# PowerBoard.net
KiCad netlist of a schematic drawn in EAGLE
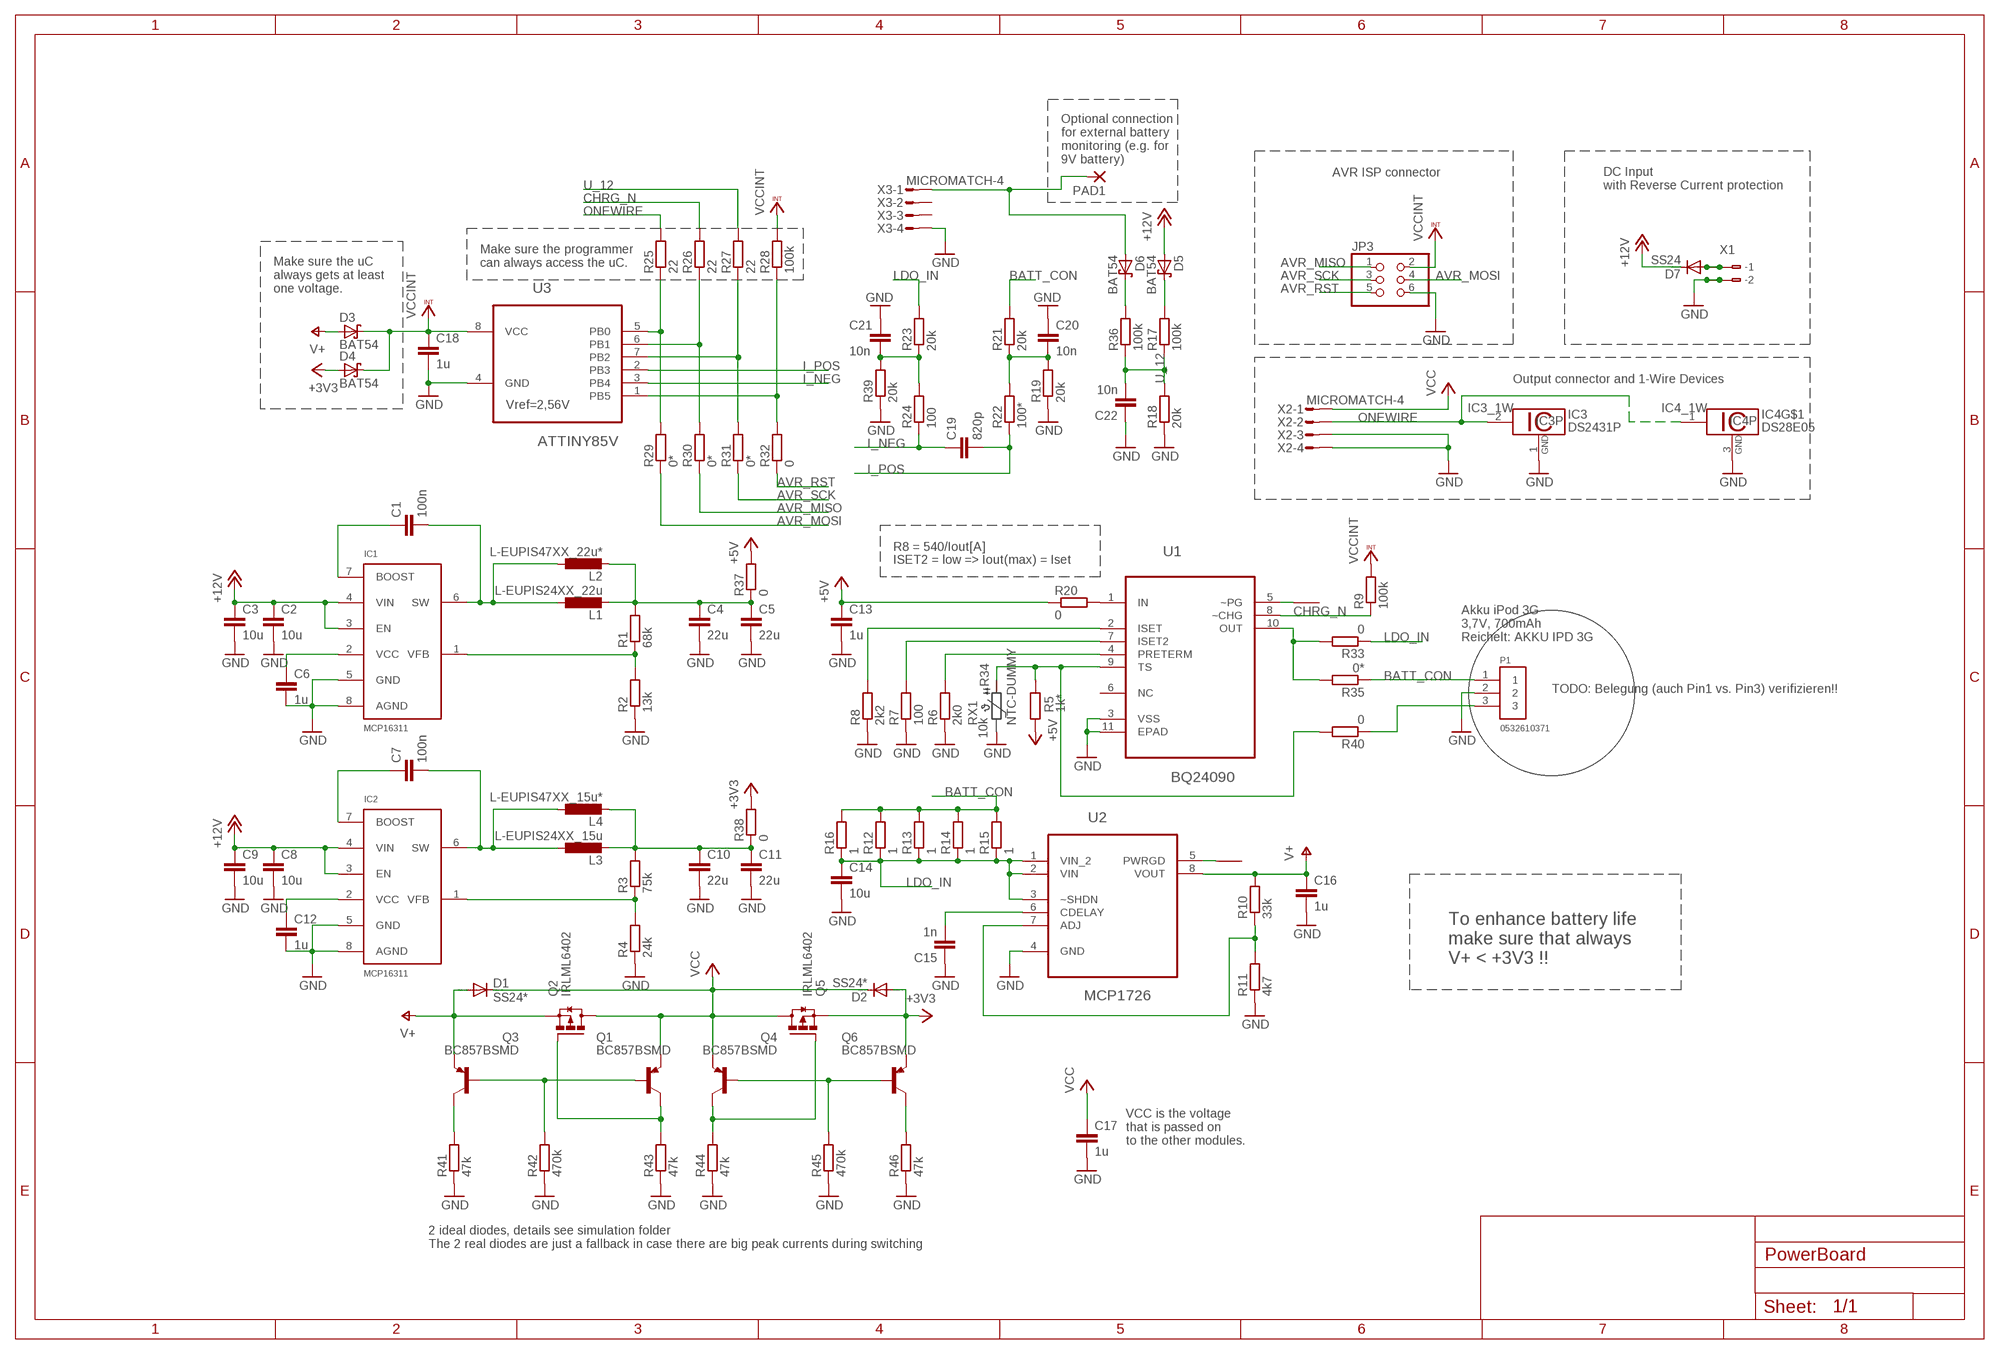
[diagram p0: schematic, sheet 1]

(export (version "E")
  (design (tool "Eeschema 10.0.6"))
  (components
    (comp (ref "C1")
      (value "100n")
      (footprint "eagle-import:C0603")
      (libsource (lib "eagle-import") (part "C-EUC0603"))
    )
    (comp (ref "C2")
      (value "10u")
      (footprint "eagle-import:C1210")
      (libsource (lib "eagle-import") (part "C-EUC1210"))
    )
    (comp (ref "C3")
      (value "10u")
      (footprint "eagle-import:C1210")
      (libsource (lib "eagle-import") (part "C-EUC1210"))
    )
    (comp (ref "C4")
      (value "22u")
      (footprint "eagle-import:C1210")
      (libsource (lib "eagle-import") (part "C-EUC1210"))
    )
    (comp (ref "C5")
      (value "22u")
      (footprint "eagle-import:C1210")
      (libsource (lib "eagle-import") (part "C-EUC1210"))
    )
    (comp (ref "C6")
      (value "1u")
      (footprint "eagle-import:C0603")
      (libsource (lib "eagle-import") (part "C-EUC0603"))
    )
    (comp (ref "C7")
      (value "100n")
      (footprint "eagle-import:C0603")
      (libsource (lib "eagle-import") (part "C-EUC0603"))
    )
    (comp (ref "C8")
      (value "10u")
      (footprint "eagle-import:C1210")
      (libsource (lib "eagle-import") (part "C-EUC1210"))
    )
    (comp (ref "C9")
      (value "10u")
      (footprint "eagle-import:C1210")
      (libsource (lib "eagle-import") (part "C-EUC1210"))
    )
    (comp (ref "C10")
      (value "22u")
      (footprint "eagle-import:C1210")
      (libsource (lib "eagle-import") (part "C-EUC1210"))
    )
    (comp (ref "C11")
      (value "22u")
      (footprint "eagle-import:C1210")
      (libsource (lib "eagle-import") (part "C-EUC1210"))
    )
    (comp (ref "C12")
      (value "1u")
      (footprint "eagle-import:C0603")
      (libsource (lib "eagle-import") (part "C-EUC0603"))
    )
    (comp (ref "C13")
      (value "1u")
      (footprint "eagle-import:C0603")
      (libsource (lib "eagle-import") (part "C-EUC0603"))
    )
    (comp (ref "C14")
      (value "10u")
      (footprint "eagle-import:C1210")
      (libsource (lib "eagle-import") (part "C-EUC1210"))
    )
    (comp (ref "C15")
      (value "1n")
      (footprint "eagle-import:C0603")
      (libsource (lib "eagle-import") (part "C-EUC0603"))
    )
    (comp (ref "C16")
      (value "1u")
      (footprint "eagle-import:C0603")
      (libsource (lib "eagle-import") (part "C-EUC0603"))
    )
    (comp (ref "C17")
      (value "1u")
      (footprint "eagle-import:C0603")
      (libsource (lib "eagle-import") (part "C-EUC0603"))
    )
    (comp (ref "C18")
      (value "1u")
      (footprint "eagle-import:C0603")
      (libsource (lib "eagle-import") (part "C-EUC0603"))
    )
    (comp (ref "C19")
      (value "820p")
      (footprint "eagle-import:C0603")
      (libsource (lib "eagle-import") (part "C-EUC0603"))
    )
    (comp (ref "C20")
      (value "10n")
      (footprint "eagle-import:C0603")
      (libsource (lib "eagle-import") (part "C-EUC0603"))
    )
    (comp (ref "C21")
      (value "10n")
      (footprint "eagle-import:C0603")
      (libsource (lib "eagle-import") (part "C-EUC0603"))
    )
    (comp (ref "C22")
      (value "10n")
      (footprint "eagle-import:C0603")
      (libsource (lib "eagle-import") (part "C-EUC0603"))
    )
    (comp (ref "D1")
      (value "SS24*")
      (footprint "eagle-import:SMB")
      (libsource (lib "eagle-import") (part "DIODE-SMB"))
    )
    (comp (ref "D2")
      (value "SS24*")
      (footprint "eagle-import:SMB")
      (libsource (lib "eagle-import") (part "DIODE-SMB"))
    )
    (comp (ref "D3")
      (value "BAT54")
      (footprint "eagle-import:SOT23")
      (libsource (lib "eagle-import") (part "BAT54"))
    )
    (comp (ref "D4")
      (value "BAT54")
      (footprint "eagle-import:SOT23")
      (libsource (lib "eagle-import") (part "BAT54"))
    )
    (comp (ref "D5")
      (value "BAT54")
      (footprint "eagle-import:SOT23")
      (libsource (lib "eagle-import") (part "BAT54"))
    )
    (comp (ref "D6")
      (value "BAT54")
      (footprint "eagle-import:SOT23")
      (libsource (lib "eagle-import") (part "BAT54"))
    )
    (comp (ref "D7")
      (value "SS24")
      (footprint "eagle-import:SMB")
      (libsource (lib "eagle-import") (part "DIODE-SMB"))
    )
    (comp (ref "IC1")
      (value "MCP16311")
      (footprint "eagle-import:SOP65P490X110-8N")
      (libsource (lib "eagle-import") (part "MCP16311"))
    )
    (comp (ref "IC2")
      (value "MCP16311")
      (footprint "eagle-import:SOP65P490X110-8N")
      (libsource (lib "eagle-import") (part "MCP16311"))
    )
    (comp (ref "IC3")
      (value "DS2431P")
      (footprint "eagle-import:TSOC6")
      (libsource (lib "eagle-import") (part "DS2431P"))
    )
    (comp (ref "IC4")
      (value "DS28E05")
      (footprint "eagle-import:SOT23")
      (libsource (lib "eagle-import") (part "DS28E05"))
    )
    (comp (ref "JP3")
      (value "PINHD-2X3")
      (footprint "eagle-import:2X03")
      (libsource (lib "eagle-import") (part "PINHD-2X3"))
    )
    (comp (ref "L1")
      (value "L-EUPIS24XX_22u")
      (footprint "eagle-import:PIS24XX")
      (libsource (lib "eagle-import") (part "L-EUPIS24XX"))
    )
    (comp (ref "L2")
      (value "L-EUPIS47XX_22u*")
      (footprint "eagle-import:PIS47XX")
      (libsource (lib "eagle-import") (part "L-EUPIS47XX"))
    )
    (comp (ref "L3")
      (value "L-EUPIS24XX_15u")
      (footprint "eagle-import:PIS24XX")
      (libsource (lib "eagle-import") (part "L-EUPIS24XX"))
    )
    (comp (ref "L4")
      (value "L-EUPIS47XX_15u*")
      (footprint "eagle-import:PIS47XX")
      (libsource (lib "eagle-import") (part "L-EUPIS47XX"))
    )
    (comp (ref "P1")
      (value "0532610371")
      (footprint "eagle-import:MOLEX_0532610371")
      (fields (field (name "MF") "Molex"))
      (libsource (lib "eagle-import") (part "0532610371"))
    )
    (comp (ref "PAD1")
      (value "WIREPADSMD2,54-5,08")
      (footprint "eagle-import:SMD2,54-5,08")
      (libsource (lib "eagle-import") (part "WIREPADSMD2,54-5,08"))
    )
    (comp (ref "Q1")
      (value "BC857BSMD")
      (footprint "eagle-import:SOT23-BEC")
      (libsource (lib "eagle-import") (part "BC857SMDB"))
    )
    (comp (ref "Q2")
      (value "IRLML6402")
      (footprint "eagle-import:SOT23")
      (libsource (lib "eagle-import") (part "IRLML6402"))
    )
    (comp (ref "Q3")
      (value "BC857BSMD")
      (footprint "eagle-import:SOT23-BEC")
      (libsource (lib "eagle-import") (part "BC857SMDB"))
    )
    (comp (ref "Q4")
      (value "BC857BSMD")
      (footprint "eagle-import:SOT23-BEC")
      (libsource (lib "eagle-import") (part "BC857SMDB"))
    )
    (comp (ref "Q5")
      (value "IRLML6402")
      (footprint "eagle-import:SOT23")
      (libsource (lib "eagle-import") (part "IRLML6402"))
    )
    (comp (ref "Q6")
      (value "BC857BSMD")
      (footprint "eagle-import:SOT23-BEC")
      (libsource (lib "eagle-import") (part "BC857SMDB"))
    )
    (comp (ref "R1")
      (value "68k")
      (footprint "eagle-import:R0603")
      (libsource (lib "eagle-import") (part "R-EU_R0603"))
    )
    (comp (ref "R2")
      (value "13k")
      (footprint "eagle-import:R0603")
      (libsource (lib "eagle-import") (part "R-EU_R0603"))
    )
    (comp (ref "R3")
      (value "75k")
      (footprint "eagle-import:R0603")
      (libsource (lib "eagle-import") (part "R-EU_R0603"))
    )
    (comp (ref "R4")
      (value "24k")
      (footprint "eagle-import:R0603")
      (libsource (lib "eagle-import") (part "R-EU_R0603"))
    )
    (comp (ref "R5")
      (value "1k*")
      (footprint "eagle-import:R0603")
      (libsource (lib "eagle-import") (part "R-EU_R0603"))
    )
    (comp (ref "R6")
      (value "2k0")
      (footprint "eagle-import:R0603")
      (libsource (lib "eagle-import") (part "R-EU_R0603"))
    )
    (comp (ref "R7")
      (value "100")
      (footprint "eagle-import:R0603")
      (libsource (lib "eagle-import") (part "R-EU_R0603"))
    )
    (comp (ref "R8")
      (value "2k2")
      (footprint "eagle-import:R0603")
      (libsource (lib "eagle-import") (part "R-EU_R0603"))
    )
    (comp (ref "R9")
      (value "100k")
      (footprint "eagle-import:R0603")
      (libsource (lib "eagle-import") (part "R-EU_R0603"))
    )
    (comp (ref "R10")
      (value "33k")
      (footprint "eagle-import:R0603")
      (libsource (lib "eagle-import") (part "R-EU_R0603"))
    )
    (comp (ref "R11")
      (value "4k7")
      (footprint "eagle-import:R0603")
      (libsource (lib "eagle-import") (part "R-EU_R0603"))
    )
    (comp (ref "R12")
      (value "1")
      (footprint "eagle-import:R0402")
      (libsource (lib "eagle-import") (part "R-EU_R0402"))
    )
    (comp (ref "R13")
      (value "1")
      (footprint "eagle-import:R0402")
      (libsource (lib "eagle-import") (part "R-EU_R0402"))
    )
    (comp (ref "R14")
      (value "1")
      (footprint "eagle-import:R0402")
      (libsource (lib "eagle-import") (part "R-EU_R0402"))
    )
    (comp (ref "R15")
      (value "1")
      (footprint "eagle-import:R0402")
      (libsource (lib "eagle-import") (part "R-EU_R0402"))
    )
    (comp (ref "R16")
      (value "1")
      (footprint "eagle-import:R0402")
      (libsource (lib "eagle-import") (part "R-EU_R0402"))
    )
    (comp (ref "R17")
      (value "100k")
      (footprint "eagle-import:R0603")
      (libsource (lib "eagle-import") (part "R-EU_R0603"))
    )
    (comp (ref "R18")
      (value "20k")
      (footprint "eagle-import:R0603")
      (libsource (lib "eagle-import") (part "R-EU_R0603"))
    )
    (comp (ref "R19")
      (value "20k")
      (footprint "eagle-import:R0603")
      (libsource (lib "eagle-import") (part "R-EU_R0603"))
    )
    (comp (ref "R20")
      (value "0")
      (footprint "eagle-import:R0603")
      (libsource (lib "eagle-import") (part "R-EU_R0603"))
    )
    (comp (ref "R21")
      (value "20k")
      (footprint "eagle-import:R0603")
      (libsource (lib "eagle-import") (part "R-EU_R0603"))
    )
    (comp (ref "R22")
      (value "100*")
      (footprint "eagle-import:R0603")
      (libsource (lib "eagle-import") (part "R-EU_R0603"))
    )
    (comp (ref "R23")
      (value "20k")
      (footprint "eagle-import:R0603")
      (libsource (lib "eagle-import") (part "R-EU_R0603"))
    )
    (comp (ref "R24")
      (value "100")
      (footprint "eagle-import:R0603")
      (libsource (lib "eagle-import") (part "R-EU_R0603"))
    )
    (comp (ref "R25")
      (value "22")
      (footprint "eagle-import:R0402")
      (libsource (lib "eagle-import") (part "R-EU_R0402"))
    )
    (comp (ref "R26")
      (value "22")
      (footprint "eagle-import:R0402")
      (libsource (lib "eagle-import") (part "R-EU_R0402"))
    )
    (comp (ref "R27")
      (value "22")
      (footprint "eagle-import:R0402")
      (libsource (lib "eagle-import") (part "R-EU_R0402"))
    )
    (comp (ref "R28")
      (value "100k")
      (footprint "eagle-import:R0402")
      (libsource (lib "eagle-import") (part "R-EU_R0402"))
    )
    (comp (ref "R29")
      (value "0*")
      (footprint "eagle-import:R0402")
      (libsource (lib "eagle-import") (part "R-EU_R0402"))
    )
    (comp (ref "R30")
      (value "0*")
      (footprint "eagle-import:R0402")
      (libsource (lib "eagle-import") (part "R-EU_R0402"))
    )
    (comp (ref "R31")
      (value "0*")
      (footprint "eagle-import:R0402")
      (libsource (lib "eagle-import") (part "R-EU_R0402"))
    )
    (comp (ref "R32")
      (value "0")
      (footprint "eagle-import:R0402")
      (libsource (lib "eagle-import") (part "R-EU_R0402"))
    )
    (comp (ref "R33")
      (value "0")
      (footprint "eagle-import:R0603")
      (libsource (lib "eagle-import") (part "R-EU_R0603"))
    )
    (comp (ref "R34")
      (value "10k")
      (footprint "eagle-import:R0603")
      (libsource (lib "eagle-import") (part "R-EU_R0603"))
    )
    (comp (ref "R35")
      (value "0*")
      (footprint "eagle-import:R0603")
      (libsource (lib "eagle-import") (part "R-EU_R0603"))
    )
    (comp (ref "R36")
      (value "100k")
      (footprint "eagle-import:R0603")
      (libsource (lib "eagle-import") (part "R-EU_R0603"))
    )
    (comp (ref "R37")
      (value "0")
      (footprint "eagle-import:R0603")
      (libsource (lib "eagle-import") (part "R-EU_R0603"))
    )
    (comp (ref "R38")
      (value "0")
      (footprint "eagle-import:R0603")
      (libsource (lib "eagle-import") (part "R-EU_R0603"))
    )
    (comp (ref "R39")
      (value "20k")
      (footprint "eagle-import:R0603")
      (libsource (lib "eagle-import") (part "R-EU_R0603"))
    )
    (comp (ref "R40")
      (value "0")
      (footprint "eagle-import:R0603")
      (libsource (lib "eagle-import") (part "R-EU_R0603"))
    )
    (comp (ref "R41")
      (value "47k")
      (footprint "eagle-import:R0603")
      (libsource (lib "eagle-import") (part "R-EU_R0603"))
    )
    (comp (ref "R42")
      (value "470k")
      (footprint "eagle-import:R0603")
      (libsource (lib "eagle-import") (part "R-EU_R0603"))
    )
    (comp (ref "R43")
      (value "47k")
      (footprint "eagle-import:R0603")
      (libsource (lib "eagle-import") (part "R-EU_R0603"))
    )
    (comp (ref "R44")
      (value "47k")
      (footprint "eagle-import:R0603")
      (libsource (lib "eagle-import") (part "R-EU_R0603"))
    )
    (comp (ref "R45")
      (value "470k")
      (footprint "eagle-import:R0603")
      (libsource (lib "eagle-import") (part "R-EU_R0603"))
    )
    (comp (ref "R46")
      (value "47k")
      (footprint "eagle-import:R0603")
      (libsource (lib "eagle-import") (part "R-EU_R0603"))
    )
    (comp (ref "U$1")
      (value "PAD100-RND")
      (footprint "eagle-import:PAD-100-RND")
      (libsource (lib "eagle-import") (part "PAD100-RND"))
    )
    (comp (ref "U$3")
      (value "PAD100-RND")
      (footprint "eagle-import:PAD-100-RND")
      (libsource (lib "eagle-import") (part "PAD100-RND"))
    )
    (comp (ref "U1")
      (value "BQ24090")
      (footprint "eagle-import:SOP50P490X110-11N")
      (fields (field (name "MF") "Texas Instruments") (field (name "MP") "BQ24090DGQT"))
      (libsource (lib "eagle-import") (part "BQ24090DGQT"))
    )
    (comp (ref "U2")
      (value "MCP1726")
      (footprint "eagle-import:SOIC127P490X175-8N")
      (fields (field (name "MF") "Microchip") (field (name "MP") "MCP1726-3302E/SN"))
      (libsource (lib "eagle-import") (part "MCP1726-3302E/SN"))
    )
    (comp (ref "U3")
      (value "ATTINY85V")
      (footprint "eagle-import:SOIC127P798X216-8N")
      (fields (field (name "MF") "Atmel") (field (name "MP") "ATTINY85V-10SU"))
      (libsource (lib "eagle-import") (part "ATTINY85V-10SU"))
    )
    (comp (ref "X1")
      (value "233-102")
      (footprint "eagle-import:233-102")
      (libsource (lib "eagle-import") (part "233-102"))
    )
    (comp (ref "X2")
      (value "MICROMATCH-4")
      (footprint "eagle-import:MICROMATCH-4")
      (fields (field (name "MPN") "7-215464-4"))
      (libsource (lib "eagle-import") (part "MICROMATCH-4"))
    )
    (comp (ref "X3")
      (value "MICROMATCH-4")
      (footprint "eagle-import:MICROMATCH-4")
      (fields (field (name "MPN") "7-215464-4"))
      (libsource (lib "eagle-import") (part "MICROMATCH-4"))
    )
  )
  (nets
    (net (code "1") (name "+3V3") (class "Default")
      (node (ref "D2") (pin "A") (pinfunction "A_A") (pintype "passive"))
      (node (ref "D4") (pin "1") (pinfunction "A_1") (pintype "passive"))
      (node (ref "Q5") (pin "2") (pinfunction "S_2") (pintype "passive"))
      (node (ref "Q6") (pin "E") (pinfunction "E_E") (pintype "passive"))
      (node (ref "R38") (pin "2") (pinfunction "2_2") (pintype "passive"))
    )
    (net (code "2") (name "+5V") (class "Default")
      (node (ref "C13") (pin "1") (pinfunction "1_1") (pintype "passive"))
      (node (ref "R20") (pin "1") (pinfunction "1_1") (pintype "passive"))
      (node (ref "R37") (pin "2") (pinfunction "2_2") (pintype "passive"))
      (node (ref "R5") (pin "1") (pinfunction "1_1") (pintype "passive"))
    )
    (net (code "3") (name "+12V") (class "Default")
      (node (ref "C2") (pin "1") (pinfunction "1_1") (pintype "passive"))
      (node (ref "C3") (pin "1") (pinfunction "1_1") (pintype "passive"))
      (node (ref "C8") (pin "1") (pinfunction "1_1") (pintype "passive"))
      (node (ref "C9") (pin "1") (pinfunction "1_1") (pintype "passive"))
      (node (ref "D5") (pin "1") (pinfunction "A_1") (pintype "passive"))
      (node (ref "D7") (pin "C") (pinfunction "C_C") (pintype "passive"))
      (node (ref "IC1") (pin "3") (pinfunction "EN_3") (pintype "bidirectional"))
      (node (ref "IC1") (pin "4") (pinfunction "VIN_4") (pintype "bidirectional"))
      (node (ref "IC2") (pin "3") (pinfunction "EN_3") (pintype "bidirectional"))
      (node (ref "IC2") (pin "4") (pinfunction "VIN_4") (pintype "bidirectional"))
    )
    (net (code "4") (name "/AVR_MISO") (class "Default")
      (node (ref "JP3") (pin "1") (pinfunction "1_1") (pintype "passive"))
      (node (ref "R30") (pin "1") (pinfunction "1_1") (pintype "passive"))
    )
    (net (code "5") (name "/AVR_MOSI") (class "Default")
      (node (ref "JP3") (pin "4") (pinfunction "4_4") (pintype "passive"))
      (node (ref "R29") (pin "1") (pinfunction "1_1") (pintype "passive"))
    )
    (net (code "6") (name "/AVR_RST") (class "Default")
      (node (ref "JP3") (pin "5") (pinfunction "5_5") (pintype "passive"))
      (node (ref "R32") (pin "1") (pinfunction "1_1") (pintype "passive"))
    )
    (net (code "7") (name "/AVR_SCK") (class "Default")
      (node (ref "JP3") (pin "3") (pinfunction "3_3") (pintype "passive"))
      (node (ref "R31") (pin "1") (pinfunction "1_1") (pintype "passive"))
    )
    (net (code "8") (name "/BATT_CON") (class "Default")
      (node (ref "P1") (pin "1") (pinfunction "1_1") (pintype "passive"))
      (node (ref "R12") (pin "2") (pinfunction "2_2") (pintype "passive"))
      (node (ref "R13") (pin "2") (pinfunction "2_2") (pintype "passive"))
      (node (ref "R14") (pin "2") (pinfunction "2_2") (pintype "passive"))
      (node (ref "R15") (pin "2") (pinfunction "2_2") (pintype "passive"))
      (node (ref "R16") (pin "2") (pinfunction "2_2") (pintype "passive"))
      (node (ref "R21") (pin "2") (pinfunction "2_2") (pintype "passive"))
      (node (ref "R35") (pin "1") (pinfunction "1_1") (pintype "passive"))
    )
    (net (code "9") (name "/CHRG_N") (class "Default")
      (node (ref "R26") (pin "2") (pinfunction "2_2") (pintype "passive"))
      (node (ref "R9") (pin "1") (pinfunction "1_1") (pintype "passive"))
      (node (ref "U1") (pin "8") (pinfunction "~{CHG}_8") (pintype "output"))
    )
    (net (code "10") (name "/I_NEG") (class "Default")
      (node (ref "C19") (pin "1") (pinfunction "1_1") (pintype "passive"))
      (node (ref "R24") (pin "1") (pinfunction "1_1") (pintype "passive"))
      (node (ref "U3") (pin "3") (pinfunction "PB4_3") (pintype "bidirectional"))
    )
    (net (code "11") (name "/I_POS") (class "Default")
      (node (ref "C19") (pin "2") (pinfunction "2_2") (pintype "passive"))
      (node (ref "R22") (pin "1") (pinfunction "1_1") (pintype "passive"))
      (node (ref "U3") (pin "2") (pinfunction "PB3_2") (pintype "bidirectional"))
    )
    (net (code "12") (name "/LDO_IN") (class "Default")
      (node (ref "C14") (pin "1") (pinfunction "1_1") (pintype "passive"))
      (node (ref "R12") (pin "1") (pinfunction "1_1") (pintype "passive"))
      (node (ref "R13") (pin "1") (pinfunction "1_1") (pintype "passive"))
      (node (ref "R14") (pin "1") (pinfunction "1_1") (pintype "passive"))
      (node (ref "R15") (pin "1") (pinfunction "1_1") (pintype "passive"))
      (node (ref "R16") (pin "1") (pinfunction "1_1") (pintype "passive"))
      (node (ref "R23") (pin "2") (pinfunction "2_2") (pintype "passive"))
      (node (ref "R33") (pin "1") (pinfunction "1_1") (pintype "passive"))
      (node (ref "U2") (pin "1") (pinfunction "VIN_2_1") (pintype "power_in"))
      (node (ref "U2") (pin "2") (pinfunction "VIN_2") (pintype "power_in"))
      (node (ref "U2") (pin "3") (pinfunction "~{SHDN}_3") (pintype "input"))
    )
    (net (code "13") (name "/ONEWIRE") (class "Default")
      (node (ref "IC3") (pin "2") (pinfunction "1W_2") (pintype "power_in"))
      (node (ref "IC4") (pin "1") (pinfunction "1W_1") (pintype "power_in"))
      (node (ref "R25") (pin "2") (pinfunction "2_2") (pintype "passive"))
      (node (ref "X2") (pin "2") (pinfunction "S_2") (pintype "passive"))
    )
    (net (code "14") (name "/U_12") (class "Default")
      (node (ref "C22") (pin "2") (pinfunction "2_2") (pintype "passive"))
      (node (ref "R17") (pin "1") (pinfunction "1_1") (pintype "passive"))
      (node (ref "R18") (pin "2") (pinfunction "2_2") (pintype "passive"))
      (node (ref "R27") (pin "2") (pinfunction "2_2") (pintype "passive"))
      (node (ref "R36") (pin "1") (pinfunction "1_1") (pintype "passive"))
    )
    (net (code "15") (name "GND") (class "Default")
      (node (ref "C10") (pin "2") (pinfunction "2_2") (pintype "passive"))
      (node (ref "C11") (pin "2") (pinfunction "2_2") (pintype "passive"))
      (node (ref "C12") (pin "2") (pinfunction "2_2") (pintype "passive"))
      (node (ref "C13") (pin "2") (pinfunction "2_2") (pintype "passive"))
      (node (ref "C14") (pin "2") (pinfunction "2_2") (pintype "passive"))
      (node (ref "C15") (pin "1") (pinfunction "1_1") (pintype "passive"))
      (node (ref "C16") (pin "2") (pinfunction "2_2") (pintype "passive"))
      (node (ref "C17") (pin "2") (pinfunction "2_2") (pintype "passive"))
      (node (ref "C18") (pin "2") (pinfunction "2_2") (pintype "passive"))
      (node (ref "C2") (pin "2") (pinfunction "2_2") (pintype "passive"))
      (node (ref "C20") (pin "1") (pinfunction "1_1") (pintype "passive"))
      (node (ref "C21") (pin "1") (pinfunction "1_1") (pintype "passive"))
      (node (ref "C22") (pin "1") (pinfunction "1_1") (pintype "passive"))
      (node (ref "C3") (pin "2") (pinfunction "2_2") (pintype "passive"))
      (node (ref "C4") (pin "2") (pinfunction "2_2") (pintype "passive"))
      (node (ref "C5") (pin "2") (pinfunction "2_2") (pintype "passive"))
      (node (ref "C6") (pin "2") (pinfunction "2_2") (pintype "passive"))
      (node (ref "C8") (pin "2") (pinfunction "2_2") (pintype "passive"))
      (node (ref "C9") (pin "2") (pinfunction "2_2") (pintype "passive"))
      (node (ref "IC1") (pin "5") (pinfunction "GND_5") (pintype "bidirectional"))
      (node (ref "IC1") (pin "8") (pinfunction "AGND_8") (pintype "bidirectional"))
      (node (ref "IC2") (pin "5") (pinfunction "GND_5") (pintype "bidirectional"))
      (node (ref "IC2") (pin "8") (pinfunction "AGND_8") (pintype "bidirectional"))
      (node (ref "IC3") (pin "1") (pinfunction "GND_1") (pintype "power_in"))
      (node (ref "IC4") (pin "3") (pinfunction "GND_3") (pintype "power_in"))
      (node (ref "JP3") (pin "6") (pinfunction "6_6") (pintype "passive"))
      (node (ref "P1") (pin "2") (pinfunction "2_2") (pintype "passive"))
      (node (ref "R11") (pin "1") (pinfunction "1_1") (pintype "passive"))
      (node (ref "R18") (pin "1") (pinfunction "1_1") (pintype "passive"))
      (node (ref "R19") (pin "1") (pinfunction "1_1") (pintype "passive"))
      (node (ref "R2") (pin "1") (pinfunction "1_1") (pintype "passive"))
      (node (ref "R34") (pin "1") (pinfunction "1_1") (pintype "passive"))
      (node (ref "R39") (pin "1") (pinfunction "1_1") (pintype "passive"))
      (node (ref "R4") (pin "1") (pinfunction "1_1") (pintype "passive"))
      (node (ref "R41") (pin "1") (pinfunction "1_1") (pintype "passive"))
      (node (ref "R42") (pin "1") (pinfunction "1_1") (pintype "passive"))
      (node (ref "R43") (pin "1") (pinfunction "1_1") (pintype "passive"))
      (node (ref "R44") (pin "1") (pinfunction "1_1") (pintype "passive"))
      (node (ref "R45") (pin "1") (pinfunction "1_1") (pintype "passive"))
      (node (ref "R46") (pin "1") (pinfunction "1_1") (pintype "passive"))
      (node (ref "R6") (pin "1") (pinfunction "1_1") (pintype "passive"))
      (node (ref "R7") (pin "1") (pinfunction "1_1") (pintype "passive"))
      (node (ref "R8") (pin "1") (pinfunction "1_1") (pintype "passive"))
      (node (ref "U1") (pin "11") (pinfunction "EPAD_11") (pintype "passive"))
      (node (ref "U1") (pin "3") (pinfunction "VSS_3") (pintype "power_in"))
      (node (ref "U2") (pin "4") (pinfunction "GND_4") (pintype "passive"))
      (node (ref "U3") (pin "4") (pinfunction "GND_4") (pintype "passive"))
      (node (ref "X1") (pin "A2") (pinfunction "-2_A2") (pintype "passive"))
      (node (ref "X1") (pin "B2") (pinfunction "B-2_B2") (pintype "passive"))
      (node (ref "X2") (pin "3") (pinfunction "S_3") (pintype "passive"))
      (node (ref "X2") (pin "4") (pinfunction "S_4") (pintype "passive"))
      (node (ref "X3") (pin "4") (pinfunction "S_4") (pintype "passive"))
    )
    (net (code "16") (name "Net-(C20-Pad2)") (class "Default")
      (node (ref "C20") (pin "2") (pinfunction "2_2") (pintype "passive"))
      (node (ref "R19") (pin "2") (pinfunction "2_2") (pintype "passive"))
      (node (ref "R21") (pin "1") (pinfunction "1_1") (pintype "passive"))
      (node (ref "R22") (pin "2") (pinfunction "2_2") (pintype "passive"))
    )
    (net (code "17") (name "Net-(C21-Pad2)") (class "Default")
      (node (ref "C21") (pin "2") (pinfunction "2_2") (pintype "passive"))
      (node (ref "R23") (pin "1") (pinfunction "1_1") (pintype "passive"))
      (node (ref "R24") (pin "2") (pinfunction "2_2") (pintype "passive"))
      (node (ref "R39") (pin "2") (pinfunction "2_2") (pintype "passive"))
    )
    (net (code "18") (name "Net-(D5-C)") (class "Default")
      (node (ref "D5") (pin "3") (pinfunction "C_3") (pintype "passive"))
      (node (ref "R17") (pin "2") (pinfunction "2_2") (pintype "passive"))
    )
    (net (code "19") (name "Net-(D6-A)") (class "Default")
      (node (ref "D6") (pin "1") (pinfunction "A_1") (pintype "passive"))
      (node (ref "PAD1") (pin "1") (pinfunction "P_1") (pintype "passive"))
      (node (ref "X3") (pin "1") (pinfunction "S_1") (pintype "passive"))
    )
    (net (code "20") (name "Net-(D6-C)") (class "Default")
      (node (ref "D6") (pin "3") (pinfunction "C_3") (pintype "passive"))
      (node (ref "R36") (pin "2") (pinfunction "2_2") (pintype "passive"))
    )
    (net (code "21") (name "Net-(IC1-BOOST)") (class "Default")
      (node (ref "C1") (pin "1") (pinfunction "1_1") (pintype "passive"))
      (node (ref "IC1") (pin "7") (pinfunction "BOOST_7") (pintype "bidirectional"))
    )
    (net (code "22") (name "Net-(IC1-SW)") (class "Default")
      (node (ref "C1") (pin "2") (pinfunction "2_2") (pintype "passive"))
      (node (ref "IC1") (pin "6") (pinfunction "SW_6") (pintype "bidirectional"))
      (node (ref "L1") (pin "2") (pinfunction "1_2") (pintype "passive"))
      (node (ref "L2") (pin "2") (pinfunction "1_2") (pintype "passive"))
    )
    (net (code "23") (name "Net-(IC1-VCC)") (class "Default")
      (node (ref "C6") (pin "1") (pinfunction "1_1") (pintype "passive"))
      (node (ref "IC1") (pin "2") (pinfunction "VCC_2") (pintype "bidirectional"))
    )
    (net (code "24") (name "Net-(IC1-VFB)") (class "Default")
      (node (ref "IC1") (pin "1") (pinfunction "VFB_1") (pintype "bidirectional"))
      (node (ref "R1") (pin "1") (pinfunction "1_1") (pintype "passive"))
      (node (ref "R2") (pin "2") (pinfunction "2_2") (pintype "passive"))
    )
    (net (code "25") (name "Net-(IC2-BOOST)") (class "Default")
      (node (ref "C7") (pin "1") (pinfunction "1_1") (pintype "passive"))
      (node (ref "IC2") (pin "7") (pinfunction "BOOST_7") (pintype "bidirectional"))
    )
    (net (code "26") (name "Net-(IC2-SW)") (class "Default")
      (node (ref "C7") (pin "2") (pinfunction "2_2") (pintype "passive"))
      (node (ref "IC2") (pin "6") (pinfunction "SW_6") (pintype "bidirectional"))
      (node (ref "L3") (pin "2") (pinfunction "1_2") (pintype "passive"))
      (node (ref "L4") (pin "2") (pinfunction "1_2") (pintype "passive"))
    )
    (net (code "27") (name "Net-(IC2-VCC)") (class "Default")
      (node (ref "C12") (pin "1") (pinfunction "1_1") (pintype "passive"))
      (node (ref "IC2") (pin "2") (pinfunction "VCC_2") (pintype "bidirectional"))
    )
    (net (code "28") (name "Net-(IC2-VFB)") (class "Default")
      (node (ref "IC2") (pin "1") (pinfunction "VFB_1") (pintype "bidirectional"))
      (node (ref "R3") (pin "1") (pinfunction "1_1") (pintype "passive"))
      (node (ref "R4") (pin "2") (pinfunction "2_2") (pintype "passive"))
    )
    (net (code "29") (name "Net-(L1-2)") (class "Default")
      (node (ref "C4") (pin "1") (pinfunction "1_1") (pintype "passive"))
      (node (ref "C5") (pin "1") (pinfunction "1_1") (pintype "passive"))
      (node (ref "L1") (pin "1") (pinfunction "2_1") (pintype "passive"))
      (node (ref "L2") (pin "1") (pinfunction "2_1") (pintype "passive"))
      (node (ref "R1") (pin "2") (pinfunction "2_2") (pintype "passive"))
      (node (ref "R37") (pin "1") (pinfunction "1_1") (pintype "passive"))
    )
    (net (code "30") (name "Net-(L3-2)") (class "Default")
      (node (ref "C10") (pin "1") (pinfunction "1_1") (pintype "passive"))
      (node (ref "C11") (pin "1") (pinfunction "1_1") (pintype "passive"))
      (node (ref "L3") (pin "1") (pinfunction "2_1") (pintype "passive"))
      (node (ref "L4") (pin "1") (pinfunction "2_1") (pintype "passive"))
      (node (ref "R3") (pin "2") (pinfunction "2_2") (pintype "passive"))
      (node (ref "R38") (pin "1") (pinfunction "1_1") (pintype "passive"))
    )
    (net (code "31") (name "Net-(P1-Pad3)") (class "Default")
      (node (ref "P1") (pin "3") (pinfunction "3_3") (pintype "passive"))
      (node (ref "R40") (pin "1") (pinfunction "1_1") (pintype "passive"))
    )
    (net (code "32") (name "Net-(Q1-PadB)") (class "Default")
      (node (ref "Q1") (pin "B") (pinfunction "B_B") (pintype "passive"))
      (node (ref "Q3") (pin "B") (pinfunction "B_B") (pintype "passive"))
      (node (ref "R42") (pin "2") (pinfunction "2_2") (pintype "passive"))
    )
    (net (code "33") (name "Net-(Q2-G)") (class "Default")
      (node (ref "Q1") (pin "C") (pinfunction "C_C") (pintype "passive"))
      (node (ref "Q2") (pin "1") (pinfunction "G_1") (pintype "passive"))
      (node (ref "R43") (pin "2") (pinfunction "2_2") (pintype "passive"))
    )
    (net (code "34") (name "Net-(Q3-PadC)") (class "Default")
      (node (ref "Q3") (pin "C") (pinfunction "C_C") (pintype "passive"))
      (node (ref "R41") (pin "2") (pinfunction "2_2") (pintype "passive"))
    )
    (net (code "35") (name "Net-(Q4-PadB)") (class "Default")
      (node (ref "Q4") (pin "B") (pinfunction "B_B") (pintype "passive"))
      (node (ref "Q6") (pin "B") (pinfunction "B_B") (pintype "passive"))
      (node (ref "R45") (pin "2") (pinfunction "2_2") (pintype "passive"))
    )
    (net (code "36") (name "Net-(Q5-G)") (class "Default")
      (node (ref "Q4") (pin "C") (pinfunction "C_C") (pintype "passive"))
      (node (ref "Q5") (pin "1") (pinfunction "G_1") (pintype "passive"))
      (node (ref "R44") (pin "2") (pinfunction "2_2") (pintype "passive"))
    )
    (net (code "37") (name "Net-(Q6-PadC)") (class "Default")
      (node (ref "Q6") (pin "C") (pinfunction "C_C") (pintype "passive"))
      (node (ref "R46") (pin "2") (pinfunction "2_2") (pintype "passive"))
    )
    (net (code "38") (name "Net-(U1-IN)") (class "Default")
      (node (ref "R20") (pin "2") (pinfunction "2_2") (pintype "passive"))
      (node (ref "U1") (pin "1") (pinfunction "IN_1") (pintype "input"))
    )
    (net (code "39") (name "Net-(U1-ISET)") (class "Default")
      (node (ref "R8") (pin "2") (pinfunction "2_2") (pintype "passive"))
      (node (ref "U1") (pin "2") (pinfunction "ISET_2") (pintype "input"))
    )
    (net (code "40") (name "Net-(U1-ISET2)") (class "Default")
      (node (ref "R7") (pin "2") (pinfunction "2_2") (pintype "passive"))
      (node (ref "U1") (pin "7") (pinfunction "ISET2_7") (pintype "input"))
    )
    (net (code "41") (name "Net-(U1-OUT)") (class "Default")
      (node (ref "R33") (pin "2") (pinfunction "2_2") (pintype "passive"))
      (node (ref "R35") (pin "2") (pinfunction "2_2") (pintype "passive"))
      (node (ref "U1") (pin "10") (pinfunction "OUT_10") (pintype "output"))
    )
    (net (code "42") (name "Net-(U1-PRETERM)") (class "Default")
      (node (ref "R6") (pin "2") (pinfunction "2_2") (pintype "passive"))
      (node (ref "U1") (pin "4") (pinfunction "PRETERM_4") (pintype "input"))
    )
    (net (code "43") (name "Net-(U1-TS)") (class "Default")
      (node (ref "R34") (pin "2") (pinfunction "2_2") (pintype "passive"))
      (node (ref "R40") (pin "2") (pinfunction "2_2") (pintype "passive"))
      (node (ref "R5") (pin "2") (pinfunction "2_2") (pintype "passive"))
      (node (ref "U1") (pin "9") (pinfunction "TS_9") (pintype "input"))
    )
    (net (code "44") (name "Net-(U1-~{PG})") (class "Default")
      (node (ref "U$1") (pin "P$1") (pinfunction "P$1_P$1") (pintype "bidirectional"))
      (node (ref "U1") (pin "5") (pinfunction "~{PG}_5") (pintype "output"))
    )
    (net (code "45") (name "Net-(U2-ADJ)") (class "Default")
      (node (ref "R10") (pin "1") (pinfunction "1_1") (pintype "passive"))
      (node (ref "R11") (pin "2") (pinfunction "2_2") (pintype "passive"))
      (node (ref "U2") (pin "7") (pinfunction "ADJ_7") (pintype "input"))
    )
    (net (code "46") (name "Net-(U2-CDELAY)") (class "Default")
      (node (ref "C15") (pin "2") (pinfunction "2_2") (pintype "passive"))
      (node (ref "U2") (pin "6") (pinfunction "CDELAY_6") (pintype "input"))
    )
    (net (code "47") (name "Net-(U2-PWRGD)") (class "Default")
      (node (ref "U$3") (pin "P$1") (pinfunction "P$1_P$1") (pintype "bidirectional"))
      (node (ref "U2") (pin "5") (pinfunction "PWRGD_5") (pintype "output"))
    )
    (net (code "48") (name "Net-(U3-PB0)") (class "Default")
      (node (ref "R25") (pin "1") (pinfunction "1_1") (pintype "passive"))
      (node (ref "R29") (pin "2") (pinfunction "2_2") (pintype "passive"))
      (node (ref "U3") (pin "5") (pinfunction "PB0_5") (pintype "bidirectional"))
    )
    (net (code "49") (name "Net-(U3-PB1)") (class "Default")
      (node (ref "R26") (pin "1") (pinfunction "1_1") (pintype "passive"))
      (node (ref "R30") (pin "2") (pinfunction "2_2") (pintype "passive"))
      (node (ref "U3") (pin "6") (pinfunction "PB1_6") (pintype "bidirectional"))
    )
    (net (code "50") (name "Net-(U3-PB2)") (class "Default")
      (node (ref "R27") (pin "1") (pinfunction "1_1") (pintype "passive"))
      (node (ref "R31") (pin "2") (pinfunction "2_2") (pintype "passive"))
      (node (ref "U3") (pin "7") (pinfunction "PB2_7") (pintype "bidirectional"))
    )
    (net (code "51") (name "Net-(U3-PB5)") (class "Default")
      (node (ref "R28") (pin "1") (pinfunction "1_1") (pintype "passive"))
      (node (ref "R32") (pin "2") (pinfunction "2_2") (pintype "passive"))
      (node (ref "U3") (pin "1") (pinfunction "PB5_1") (pintype "bidirectional"))
    )
    (net (code "52") (name "Net-(X1--1)") (class "Default")
      (node (ref "D7") (pin "A") (pinfunction "A_A") (pintype "passive"))
      (node (ref "X1") (pin "A1") (pinfunction "-1_A1") (pintype "passive"))
      (node (ref "X1") (pin "B1") (pinfunction "B-1_B1") (pintype "passive"))
    )
    (net (code "53") (name "V+") (class "Default")
      (node (ref "C16") (pin "1") (pinfunction "1_1") (pintype "passive"))
      (node (ref "D1") (pin "A") (pinfunction "A_A") (pintype "passive"))
      (node (ref "D3") (pin "1") (pinfunction "A_1") (pintype "passive"))
      (node (ref "Q2") (pin "2") (pinfunction "S_2") (pintype "passive"))
      (node (ref "Q3") (pin "E") (pinfunction "E_E") (pintype "passive"))
      (node (ref "R10") (pin "2") (pinfunction "2_2") (pintype "passive"))
      (node (ref "U2") (pin "8") (pinfunction "VOUT_8") (pintype "output"))
    )
    (net (code "54") (name "VCC") (class "Default")
      (node (ref "C17") (pin "1") (pinfunction "1_1") (pintype "passive"))
      (node (ref "D1") (pin "C") (pinfunction "C_C") (pintype "passive"))
      (node (ref "D2") (pin "C") (pinfunction "C_C") (pintype "passive"))
      (node (ref "Q1") (pin "E") (pinfunction "E_E") (pintype "passive"))
      (node (ref "Q2") (pin "3") (pinfunction "D_3") (pintype "passive"))
      (node (ref "Q4") (pin "E") (pinfunction "E_E") (pintype "passive"))
      (node (ref "Q5") (pin "3") (pinfunction "D_3") (pintype "passive"))
      (node (ref "X2") (pin "1") (pinfunction "S_1") (pintype "passive"))
    )
    (net (code "55") (name "VCCINT") (class "Default")
      (node (ref "C18") (pin "1") (pinfunction "1_1") (pintype "passive"))
      (node (ref "D3") (pin "3") (pinfunction "C_3") (pintype "passive"))
      (node (ref "D4") (pin "3") (pinfunction "C_3") (pintype "passive"))
      (node (ref "JP3") (pin "2") (pinfunction "2_2") (pintype "passive"))
      (node (ref "R28") (pin "2") (pinfunction "2_2") (pintype "passive"))
      (node (ref "R9") (pin "2") (pinfunction "2_2") (pintype "passive"))
      (node (ref "U3") (pin "8") (pinfunction "VCC_8") (pintype "power_in"))
    )
    (net (code "56") (name "unconnected-(U1-NC-Pad6)") (class "Default")
      (node (ref "U1") (pin "6") (pinfunction "NC_6") (pintype "no_connect"))
    )
    (net (code "57") (name "unconnected-(X3B-S-Pad2)") (class "Default")
      (node (ref "X3") (pin "2") (pinfunction "S_2") (pintype "passive"))
    )
    (net (code "58") (name "unconnected-(X3C-S-Pad3)") (class "Default")
      (node (ref "X3") (pin "3") (pinfunction "S_3") (pintype "passive"))
    )
  )
)
